# SMIW_Project_schematic.net
KiCad netlist of a schematic drawn in EAGLE
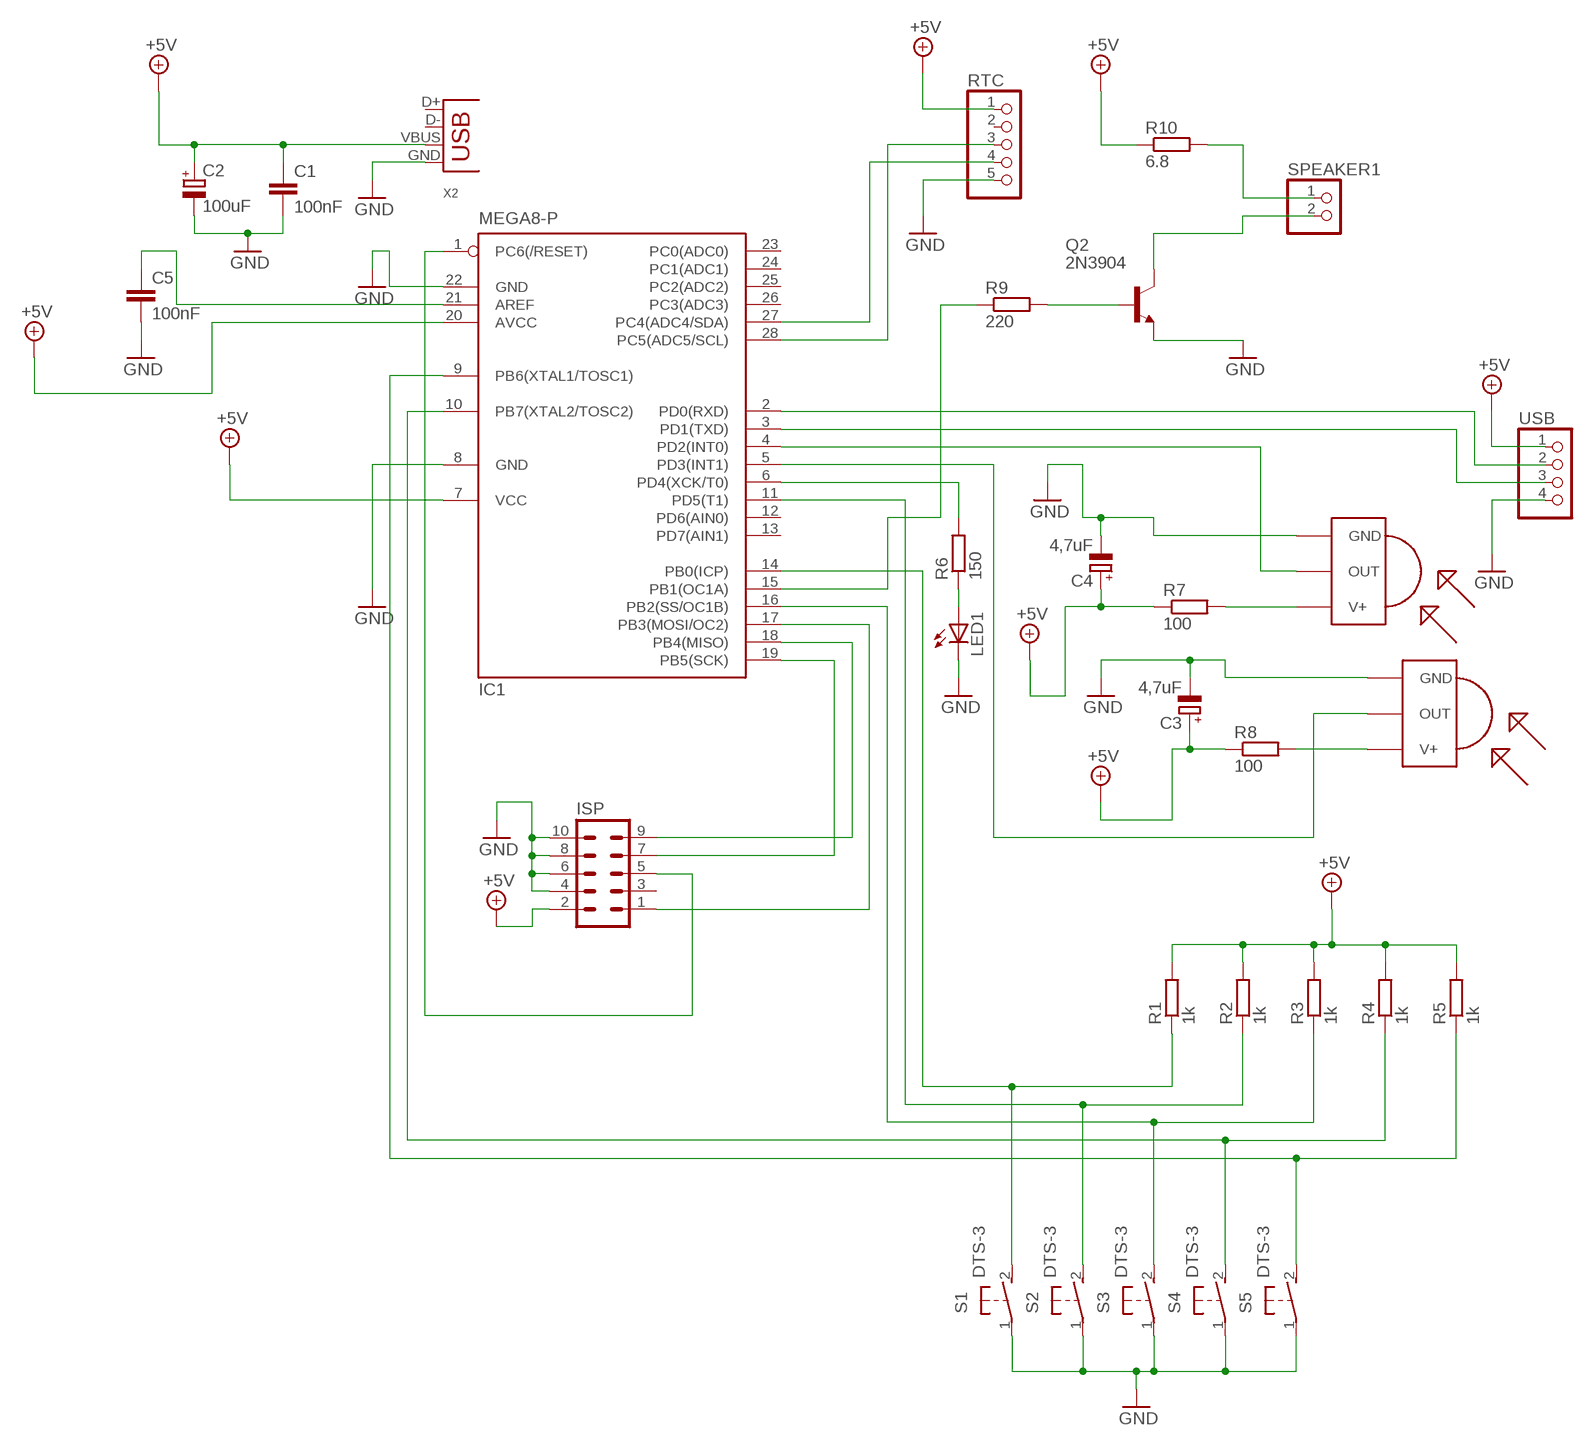
[diagram p0: schematic, sheet 1]

(export (version "E")
  (design (tool "Eeschema 10.0.6"))
  (components
    (comp (ref "C1")
      (value "100nF")
      (footprint "eagle-import:C2.5-3")
      (libsource (lib "eagle-import") (part "C2,5-3"))
    )
    (comp (ref "C2")
      (value "100uF")
      (footprint "eagle-import:TT2D6")
      (libsource (lib "eagle-import") (part "CPOL-EUTT2D6"))
    )
    (comp (ref "C3")
      (value "4,7uF")
      (footprint "eagle-import:TT2D6")
      (libsource (lib "eagle-import") (part "CPOL-EUTT2D6"))
    )
    (comp (ref "C4")
      (value "4,7uF")
      (footprint "eagle-import:TT2D6")
      (libsource (lib "eagle-import") (part "CPOL-EUTT2D6"))
    )
    (comp (ref "C5")
      (value "100nF")
      (footprint "eagle-import:C2.5-3")
      (libsource (lib "eagle-import") (part "C2,5-3"))
    )
    (comp (ref "IC1")
      (value "MEGA8-P")
      (footprint "eagle-import:DIL28-3")
      (libsource (lib "eagle-import") (part "MEGA8-P"))
    )
    (comp (ref "IRR1")
      (value "TSOP4836")
      (footprint "eagle-import:TSOP18XX")
      (libsource (lib "eagle-import") (part "TSOP4836"))
    )
    (comp (ref "IRR2")
      (value "TSOP4836")
      (footprint "eagle-import:TSOP18XX")
      (libsource (lib "eagle-import") (part "TSOP4836"))
    )
    (comp (ref "ISP")
      (value "ML10")
      (footprint "eagle-import:ML10")
      (libsource (lib "eagle-import") (part "ML10"))
    )
    (comp (ref "LED1")
      (value "LED3MM")
      (footprint "eagle-import:LED3MM")
      (libsource (lib "eagle-import") (part "LED3MM"))
    )
    (comp (ref "Q2")
      (value "2N3904")
      (footprint "eagle-import:TO92")
      (libsource (lib "eagle-import") (part "2N3904"))
    )
    (comp (ref "R1")
      (value "1k")
      (footprint "eagle-import:0207_5V")
      (libsource (lib "eagle-import") (part "R-EU_0207/5V"))
    )
    (comp (ref "R2")
      (value "1k")
      (footprint "eagle-import:0207_5V")
      (libsource (lib "eagle-import") (part "R-EU_0207/5V"))
    )
    (comp (ref "R3")
      (value "1k")
      (footprint "eagle-import:0207_5V")
      (libsource (lib "eagle-import") (part "R-EU_0207/5V"))
    )
    (comp (ref "R4")
      (value "1k")
      (footprint "eagle-import:0207_5V")
      (libsource (lib "eagle-import") (part "R-EU_0207/5V"))
    )
    (comp (ref "R5")
      (value "1k")
      (footprint "eagle-import:0207_5V")
      (libsource (lib "eagle-import") (part "R-EU_0207/5V"))
    )
    (comp (ref "R6")
      (value "150")
      (footprint "eagle-import:0207_5V")
      (libsource (lib "eagle-import") (part "R-EU_0207/5V"))
    )
    (comp (ref "R7")
      (value "100")
      (footprint "eagle-import:0207_5V")
      (libsource (lib "eagle-import") (part "R-EU_0207/5V"))
    )
    (comp (ref "R8")
      (value "100")
      (footprint "eagle-import:0207_5V")
      (libsource (lib "eagle-import") (part "R-EU_0207/5V"))
    )
    (comp (ref "R9")
      (value "220")
      (footprint "eagle-import:0207_5V")
      (libsource (lib "eagle-import") (part "R-EU_0207/5V"))
    )
    (comp (ref "R10")
      (value "6.8")
      (footprint "eagle-import:0207_5V")
      (libsource (lib "eagle-import") (part "R-EU_0207/5V"))
    )
    (comp (ref "RTC")
      (value "PINHD-1X5")
      (footprint "eagle-import:1X05")
      (libsource (lib "eagle-import") (part "PINHD-1X5"))
    )
    (comp (ref "S1")
      (value "DTS-3")
      (footprint "eagle-import:DTS-3")
      (libsource (lib "eagle-import") (part "DTS-3"))
    )
    (comp (ref "S2")
      (value "DTS-3")
      (footprint "eagle-import:DTS-3")
      (libsource (lib "eagle-import") (part "DTS-3"))
    )
    (comp (ref "S3")
      (value "DTS-3")
      (footprint "eagle-import:DTS-3")
      (libsource (lib "eagle-import") (part "DTS-3"))
    )
    (comp (ref "S4")
      (value "DTS-3")
      (footprint "eagle-import:DTS-3")
      (libsource (lib "eagle-import") (part "DTS-3"))
    )
    (comp (ref "S5")
      (value "DTS-3")
      (footprint "eagle-import:DTS-3")
      (libsource (lib "eagle-import") (part "DTS-3"))
    )
    (comp (ref "SPEAKER1")
      (value "PINHD-1X2")
      (footprint "eagle-import:1X02")
      (libsource (lib "eagle-import") (part "PINHD-1X2"))
    )
    (comp (ref "USB")
      (value "PINHD-1X4")
      (footprint "eagle-import:1X04")
      (libsource (lib "eagle-import") (part "PINHD-1X4"))
    )
    (comp (ref "X2")
      (value "USB-B-H")
      (footprint "eagle-import:USB-B-H")
      (libsource (lib "eagle-import") (part "USB-B-H"))
    )
  )
  (nets
    (net (code "1") (name "+5V") (class "Default")
      (node (ref "C1") (pin "1") (pinfunction "1_1") (pintype "passive"))
      (node (ref "C2") (pin "+") (pinfunction "+_+") (pintype "passive"))
      (node (ref "C3") (pin "+") (pinfunction "+_+") (pintype "passive"))
      (node (ref "C4") (pin "+") (pinfunction "+_+") (pintype "passive"))
      (node (ref "IC1") (pin "20") (pinfunction "AVCC_20") (pintype "power_in"))
      (node (ref "IC1") (pin "7") (pinfunction "VCC_7") (pintype "power_in"))
      (node (ref "ISP") (pin "2") (pinfunction "2_2") (pintype "passive"))
      (node (ref "R1") (pin "2") (pinfunction "2_2") (pintype "passive"))
      (node (ref "R10") (pin "1") (pinfunction "1_1") (pintype "passive"))
      (node (ref "R2") (pin "2") (pinfunction "2_2") (pintype "passive"))
      (node (ref "R3") (pin "2") (pinfunction "2_2") (pintype "passive"))
      (node (ref "R4") (pin "2") (pinfunction "2_2") (pintype "passive"))
      (node (ref "R5") (pin "2") (pinfunction "2_2") (pintype "passive"))
      (node (ref "R7") (pin "1") (pinfunction "1_1") (pintype "passive"))
      (node (ref "R8") (pin "1") (pinfunction "1_1") (pintype "passive"))
      (node (ref "RTC") (pin "1") (pinfunction "1_1") (pintype "passive"))
      (node (ref "USB") (pin "1") (pinfunction "1_1") (pintype "passive"))
      (node (ref "X2") (pin "VBUS") (pinfunction "VBUS_VBUS") (pintype "bidirectional"))
    )
    (net (code "2") (name "GND") (class "Default")
      (node (ref "C1") (pin "2") (pinfunction "2_2") (pintype "passive"))
      (node (ref "C2") (pin "-") (pinfunction "-_-") (pintype "passive"))
      (node (ref "C3") (pin "-") (pinfunction "-_-") (pintype "passive"))
      (node (ref "C4") (pin "-") (pinfunction "-_-") (pintype "passive"))
      (node (ref "C5") (pin "2") (pinfunction "2_2") (pintype "passive"))
      (node (ref "IC1") (pin "22") (pinfunction "GND_22") (pintype "power_in"))
      (node (ref "IC1") (pin "8") (pinfunction "GND_8") (pintype "power_in"))
      (node (ref "IRR1") (pin "GND") (pinfunction "GND_GND") (pintype "bidirectional"))
      (node (ref "IRR2") (pin "GND") (pinfunction "GND_GND") (pintype "bidirectional"))
      (node (ref "ISP") (pin "10") (pinfunction "10_10") (pintype "passive"))
      (node (ref "ISP") (pin "4") (pinfunction "4_4") (pintype "passive"))
      (node (ref "ISP") (pin "6") (pinfunction "6_6") (pintype "passive"))
      (node (ref "ISP") (pin "8") (pinfunction "8_8") (pintype "passive"))
      (node (ref "LED1") (pin "K") (pinfunction "C_K") (pintype "passive"))
      (node (ref "Q2") (pin "3") (pinfunction "E_3") (pintype "passive"))
      (node (ref "RTC") (pin "5") (pinfunction "5_5") (pintype "passive"))
      (node (ref "S1") (pin "1") (pinfunction "1_1") (pintype "passive"))
      (node (ref "S2") (pin "1") (pinfunction "1_1") (pintype "passive"))
      (node (ref "S3") (pin "1") (pinfunction "1_1") (pintype "passive"))
      (node (ref "S4") (pin "1") (pinfunction "1_1") (pintype "passive"))
      (node (ref "S5") (pin "1") (pinfunction "1_1") (pintype "passive"))
      (node (ref "USB") (pin "4") (pinfunction "4_4") (pintype "passive"))
      (node (ref "X2") (pin "GND") (pinfunction "GND_GND") (pintype "bidirectional"))
    )
    (net (code "3") (name "Net-(IC1-AREF)") (class "Default")
      (node (ref "C5") (pin "1") (pinfunction "1_1") (pintype "passive"))
      (node (ref "IC1") (pin "21") (pinfunction "AREF_21") (pintype "passive"))
    )
    (net (code "4") (name "Net-(IC1-PB0(ICP))") (class "Default")
      (node (ref "IC1") (pin "14") (pinfunction "PB0(ICP)_14") (pintype "bidirectional"))
      (node (ref "R1") (pin "1") (pinfunction "1_1") (pintype "passive"))
      (node (ref "S1") (pin "2") (pinfunction "2_2") (pintype "passive"))
    )
    (net (code "5") (name "Net-(IC1-PB1(OC1A))") (class "Default")
      (node (ref "IC1") (pin "15") (pinfunction "PB1(OC1A)_15") (pintype "bidirectional"))
      (node (ref "R9") (pin "1") (pinfunction "1_1") (pintype "passive"))
    )
    (net (code "6") (name "Net-(IC1-PB2(SS{slash}OC1B))") (class "Default")
      (node (ref "IC1") (pin "16") (pinfunction "PB2(SS/OC1B)_16") (pintype "bidirectional"))
      (node (ref "R3") (pin "1") (pinfunction "1_1") (pintype "passive"))
      (node (ref "S3") (pin "2") (pinfunction "2_2") (pintype "passive"))
    )
    (net (code "7") (name "Net-(IC1-PB3(MOSI{slash}OC2))") (class "Default")
      (node (ref "IC1") (pin "17") (pinfunction "PB3(MOSI/OC2)_17") (pintype "bidirectional"))
      (node (ref "ISP") (pin "1") (pinfunction "1_1") (pintype "passive"))
    )
    (net (code "8") (name "Net-(IC1-PB4(MISO))") (class "Default")
      (node (ref "IC1") (pin "18") (pinfunction "PB4(MISO)_18") (pintype "bidirectional"))
      (node (ref "ISP") (pin "9") (pinfunction "9_9") (pintype "passive"))
    )
    (net (code "9") (name "Net-(IC1-PB5(SCK))") (class "Default")
      (node (ref "IC1") (pin "19") (pinfunction "PB5(SCK)_19") (pintype "bidirectional"))
      (node (ref "ISP") (pin "7") (pinfunction "7_7") (pintype "passive"))
    )
    (net (code "10") (name "Net-(IC1-PB6(XTAL1{slash}TOSC1))") (class "Default")
      (node (ref "IC1") (pin "9") (pinfunction "PB6(XTAL1/TOSC1)_9") (pintype "bidirectional"))
      (node (ref "R5") (pin "1") (pinfunction "1_1") (pintype "passive"))
      (node (ref "S5") (pin "2") (pinfunction "2_2") (pintype "passive"))
    )
    (net (code "11") (name "Net-(IC1-PB7(XTAL2{slash}TOSC2))") (class "Default")
      (node (ref "IC1") (pin "10") (pinfunction "PB7(XTAL2/TOSC2)_10") (pintype "bidirectional"))
      (node (ref "R4") (pin "1") (pinfunction "1_1") (pintype "passive"))
      (node (ref "S4") (pin "2") (pinfunction "2_2") (pintype "passive"))
    )
    (net (code "12") (name "Net-(IC1-PC4(ADC4{slash}SDA))") (class "Default")
      (node (ref "IC1") (pin "27") (pinfunction "PC4(ADC4/SDA)_27") (pintype "bidirectional"))
      (node (ref "RTC") (pin "4") (pinfunction "4_4") (pintype "passive"))
    )
    (net (code "13") (name "Net-(IC1-PC5(ADC5{slash}SCL))") (class "Default")
      (node (ref "IC1") (pin "28") (pinfunction "PC5(ADC5/SCL)_28") (pintype "bidirectional"))
      (node (ref "RTC") (pin "3") (pinfunction "3_3") (pintype "passive"))
    )
    (net (code "14") (name "Net-(IC1-PC6({slash}RESET))") (class "Default")
      (node (ref "IC1") (pin "1") (pinfunction "PC6(/RESET)_1") (pintype "bidirectional"))
      (node (ref "ISP") (pin "5") (pinfunction "5_5") (pintype "passive"))
    )
    (net (code "15") (name "Net-(IC1-PD0(RXD))") (class "Default")
      (node (ref "IC1") (pin "2") (pinfunction "PD0(RXD)_2") (pintype "bidirectional"))
      (node (ref "USB") (pin "2") (pinfunction "2_2") (pintype "passive"))
    )
    (net (code "16") (name "Net-(IC1-PD1(TXD))") (class "Default")
      (node (ref "IC1") (pin "3") (pinfunction "PD1(TXD)_3") (pintype "bidirectional"))
      (node (ref "USB") (pin "3") (pinfunction "3_3") (pintype "passive"))
    )
    (net (code "17") (name "Net-(IC1-PD2(INT0))") (class "Default")
      (node (ref "IC1") (pin "4") (pinfunction "PD2(INT0)_4") (pintype "bidirectional"))
      (node (ref "IRR1") (pin "OUT") (pinfunction "OUT_OUT") (pintype "bidirectional"))
    )
    (net (code "18") (name "Net-(IC1-PD3(INT1))") (class "Default")
      (node (ref "IC1") (pin "5") (pinfunction "PD3(INT1)_5") (pintype "bidirectional"))
      (node (ref "IRR2") (pin "OUT") (pinfunction "OUT_OUT") (pintype "bidirectional"))
    )
    (net (code "19") (name "Net-(IC1-PD4(XCK{slash}T0))") (class "Default")
      (node (ref "IC1") (pin "6") (pinfunction "PD4(XCK/T0)_6") (pintype "bidirectional"))
      (node (ref "R6") (pin "2") (pinfunction "2_2") (pintype "passive"))
    )
    (net (code "20") (name "Net-(IC1-PD5(T1))") (class "Default")
      (node (ref "IC1") (pin "11") (pinfunction "PD5(T1)_11") (pintype "bidirectional"))
      (node (ref "R2") (pin "1") (pinfunction "1_1") (pintype "passive"))
      (node (ref "S2") (pin "2") (pinfunction "2_2") (pintype "passive"))
    )
    (net (code "21") (name "Net-(IRR1-V+)") (class "Default")
      (node (ref "IRR1") (pin "VCC") (pinfunction "V+_VCC") (pintype "bidirectional"))
      (node (ref "R7") (pin "2") (pinfunction "2_2") (pintype "passive"))
    )
    (net (code "22") (name "Net-(IRR2-V+)") (class "Default")
      (node (ref "IRR2") (pin "VCC") (pinfunction "V+_VCC") (pintype "bidirectional"))
      (node (ref "R8") (pin "2") (pinfunction "2_2") (pintype "passive"))
    )
    (net (code "23") (name "Net-(LED1-PadA)") (class "Default")
      (node (ref "LED1") (pin "A") (pinfunction "A_A") (pintype "passive"))
      (node (ref "R6") (pin "1") (pinfunction "1_1") (pintype "passive"))
    )
    (net (code "24") (name "Net-(Q2-B)") (class "Default")
      (node (ref "Q2") (pin "2") (pinfunction "B_2") (pintype "passive"))
      (node (ref "R9") (pin "2") (pinfunction "2_2") (pintype "passive"))
    )
    (net (code "25") (name "Net-(Q2-C)") (class "Default")
      (node (ref "Q2") (pin "1") (pinfunction "C_1") (pintype "passive"))
      (node (ref "SPEAKER1") (pin "2") (pinfunction "2_2") (pintype "passive"))
    )
    (net (code "26") (name "Net-(R10-Pad2)") (class "Default")
      (node (ref "R10") (pin "2") (pinfunction "2_2") (pintype "passive"))
      (node (ref "SPEAKER1") (pin "1") (pinfunction "1_1") (pintype "passive"))
    )
    (net (code "27") (name "unconnected-(IC1-PC0(ADC0)-Pad23)") (class "Default")
      (node (ref "IC1") (pin "23") (pinfunction "PC0(ADC0)_23") (pintype "bidirectional"))
    )
    (net (code "28") (name "unconnected-(IC1-PC1(ADC1)-Pad24)") (class "Default")
      (node (ref "IC1") (pin "24") (pinfunction "PC1(ADC1)_24") (pintype "bidirectional"))
    )
    (net (code "29") (name "unconnected-(IC1-PC2(ADC2)-Pad25)") (class "Default")
      (node (ref "IC1") (pin "25") (pinfunction "PC2(ADC2)_25") (pintype "bidirectional"))
    )
    (net (code "30") (name "unconnected-(IC1-PC3(ADC3)-Pad26)") (class "Default")
      (node (ref "IC1") (pin "26") (pinfunction "PC3(ADC3)_26") (pintype "bidirectional"))
    )
    (net (code "31") (name "unconnected-(IC1-PD6(AIN0)-Pad12)") (class "Default")
      (node (ref "IC1") (pin "12") (pinfunction "PD6(AIN0)_12") (pintype "bidirectional"))
    )
    (net (code "32") (name "unconnected-(IC1-PD7(AIN1)-Pad13)") (class "Default")
      (node (ref "IC1") (pin "13") (pinfunction "PD7(AIN1)_13") (pintype "bidirectional"))
    )
    (net (code "33") (name "unconnected-(ISP-Pad3)") (class "Default")
      (node (ref "ISP") (pin "3") (pinfunction "3_3") (pintype "passive"))
    )
    (net (code "34") (name "unconnected-(RTC-Pad2)") (class "Default")
      (node (ref "RTC") (pin "2") (pinfunction "2_2") (pintype "passive"))
    )
    (net (code "35") (name "unconnected-(X2-PadD+)") (class "Default")
      (node (ref "X2") (pin "D+") (pinfunction "D+_D+") (pintype "bidirectional"))
    )
    (net (code "36") (name "unconnected-(X2-PadD-)") (class "Default")
      (node (ref "X2") (pin "D-") (pinfunction "D-_D-") (pintype "bidirectional"))
    )
  )
)
